# Schematic.net
KiCad netlist of a schematic drawn in EAGLE
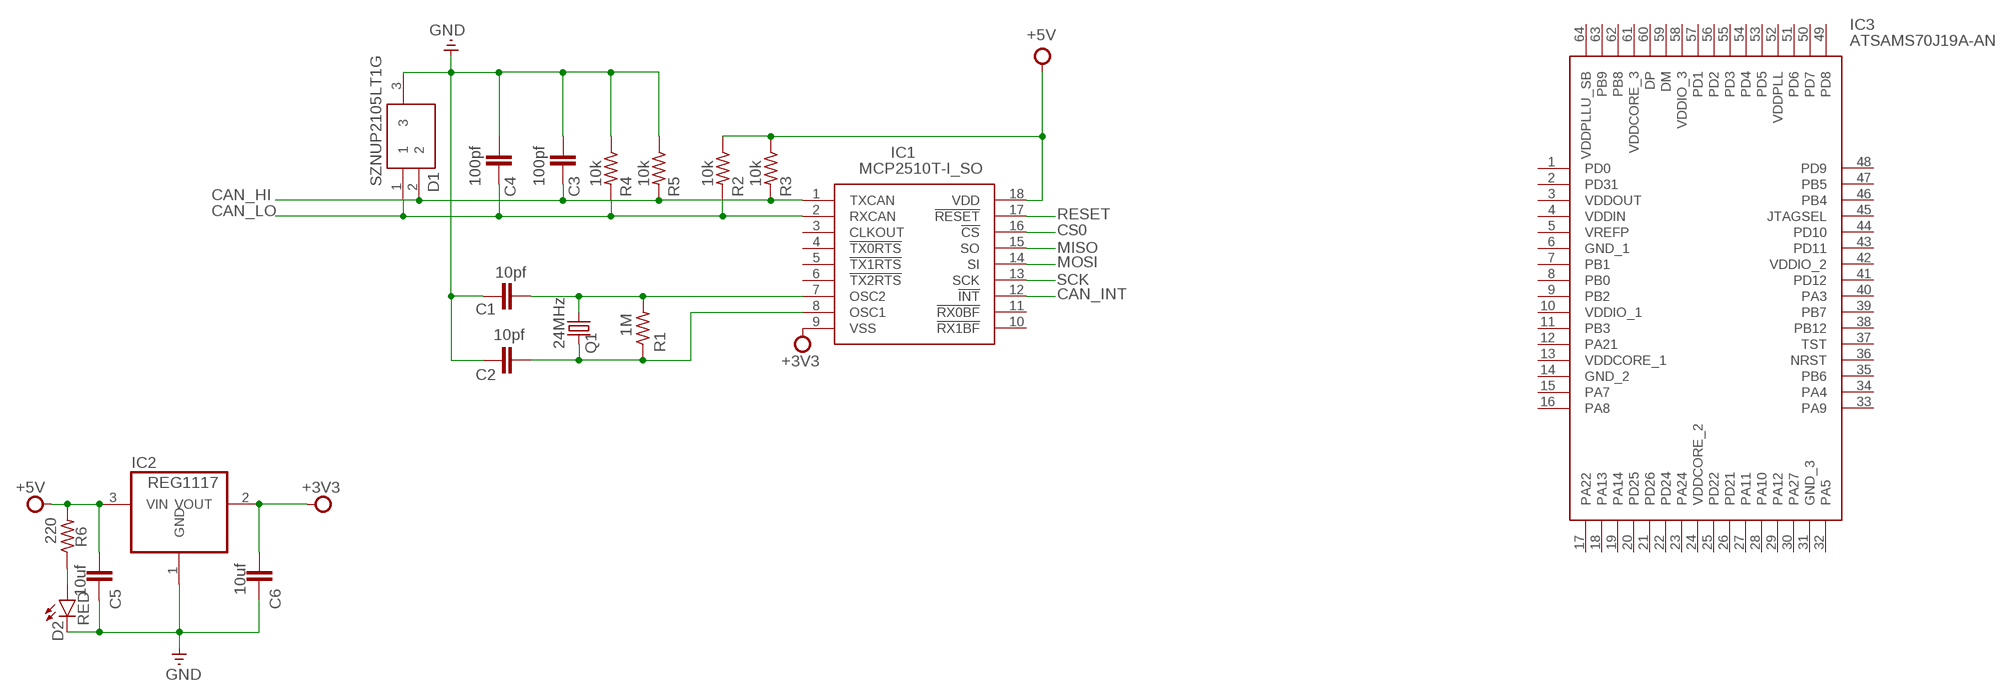
[diagram p0: schematic, sheet 1]

(export (version "E")
  (design (tool "Eeschema 10.0.6"))
  (components
    (comp (ref "C1")
      (value "10pf")
      (footprint "eagle-import:C2.5-3")
      (libsource (lib "eagle-import") (part "C2,5-3"))
    )
    (comp (ref "C2")
      (value "10pf")
      (footprint "eagle-import:C2.5-3")
      (libsource (lib "eagle-import") (part "C2,5-3"))
    )
    (comp (ref "C3")
      (value "100pf")
      (footprint "eagle-import:C2.5-3")
      (libsource (lib "eagle-import") (part "C2,5-3"))
    )
    (comp (ref "C4")
      (value "100pf")
      (footprint "eagle-import:C2.5-3")
      (libsource (lib "eagle-import") (part "C2,5-3"))
    )
    (comp (ref "C5")
      (value "10uf")
      (footprint "eagle-import:C2.5-3")
      (libsource (lib "eagle-import") (part "C2,5-3"))
    )
    (comp (ref "C6")
      (value "10uf")
      (footprint "eagle-import:C2.5-3")
      (libsource (lib "eagle-import") (part "C2,5-3"))
    )
    (comp (ref "D1")
      (value "SZNUP2105LT1G")
      (footprint "eagle-import:SOT96P237X111-3N")
      (fields (field (name "MOUSER_PART_NUMBER") "863-SZNUP2105LT1G"))
      (libsource (lib "eagle-import") (part "SZNUP2105LT1G"))
    )
    (comp (ref "D2")
      (value "RED")
      (footprint "eagle-import:LED-0402")
      (libsource (lib "eagle-import") (part "LED-RED_0402"))
    )
    (comp (ref "IC1")
      (value "MCP2510T-I_SO")
      (footprint "eagle-import:SOIC127P1030X265-18N")
      (fields
        (field (name "MANUFACTURER_PART_NUMBER") "MCP2510T-I/SO")
        (field (name "MOUSER_PART_NUMBER") "579-MCP2510T-I/SO")
      )
      (libsource (lib "eagle-import") (part "MCP2510T-I_SO"))
    )
    (comp (ref "IC2")
      (value "REG1117")
      (footprint "eagle-import:SOT223")
      (libsource (lib "eagle-import") (part "REG1117"))
    )
    (comp (ref "IC3")
      (value "ATSAMS70J19A-AN")
      (footprint "eagle-import:QFP50P1200X1200X160-64N")
      (fields (field (name "MOUSER_PART_NUMBER") "556-ATSAMS70J19A-AN"))
      (libsource (lib "eagle-import") (part "ATSAMS70J19A-AN"))
    )
    (comp (ref "Q1")
      (value "24MHz")
      (footprint "eagle-import:HC49_S")
      (libsource (lib "eagle-import") (part "CRYSTALHC49S"))
    )
    (comp (ref "R1")
      (value "1M")
      (footprint "eagle-import:0204_5")
      (libsource (lib "eagle-import") (part "R-US_0204/5"))
    )
    (comp (ref "R2")
      (value "10k")
      (footprint "eagle-import:0204_5")
      (libsource (lib "eagle-import") (part "R-US_0204/5"))
    )
    (comp (ref "R3")
      (value "10k")
      (footprint "eagle-import:0204_5")
      (libsource (lib "eagle-import") (part "R-US_0204/5"))
    )
    (comp (ref "R4")
      (value "10k")
      (footprint "eagle-import:0204_5")
      (libsource (lib "eagle-import") (part "R-US_0204/5"))
    )
    (comp (ref "R5")
      (value "10k")
      (footprint "eagle-import:0204_5")
      (libsource (lib "eagle-import") (part "R-US_0204/5"))
    )
    (comp (ref "R6")
      (value "220")
      (footprint "eagle-import:0204_5")
      (libsource (lib "eagle-import") (part "R-US_0204/5"))
    )
  )
  (nets
    (net (code "1") (name "+3V3") (class "Default")
      (node (ref "C6") (pin "1") (pinfunction "1_1") (pintype "passive"))
      (node (ref "IC1") (pin "9") (pinfunction "VSS_9") (pintype "power_in"))
      (node (ref "IC2") (pin "2") (pinfunction "VOUT_2") (pintype "output"))
    )
    (net (code "2") (name "+5V") (class "Default")
      (node (ref "C5") (pin "1") (pinfunction "1_1") (pintype "passive"))
      (node (ref "IC1") (pin "18") (pinfunction "VDD_18") (pintype "power_in"))
      (node (ref "IC2") (pin "3") (pinfunction "VIN_3") (pintype "input"))
      (node (ref "R2") (pin "1") (pinfunction "1_1") (pintype "passive"))
      (node (ref "R3") (pin "1") (pinfunction "1_1") (pintype "passive"))
      (node (ref "R6") (pin "2") (pinfunction "2_2") (pintype "passive"))
    )
    (net (code "3") (name "/CAN_HI") (class "Default")
      (node (ref "C3") (pin "1") (pinfunction "1_1") (pintype "passive"))
      (node (ref "D1") (pin "2") (pinfunction "2_2") (pintype "bidirectional"))
      (node (ref "IC1") (pin "1") (pinfunction "TXCAN_1") (pintype "bidirectional"))
      (node (ref "R3") (pin "2") (pinfunction "2_2") (pintype "passive"))
      (node (ref "R5") (pin "2") (pinfunction "2_2") (pintype "passive"))
    )
    (net (code "4") (name "/CAN_INT") (class "Default")
      (node (ref "IC1") (pin "12") (pinfunction "~{INT}_12") (pintype "input"))
    )
    (net (code "5") (name "/CAN_LO") (class "Default")
      (node (ref "C4") (pin "1") (pinfunction "1_1") (pintype "passive"))
      (node (ref "D1") (pin "1") (pinfunction "1_1") (pintype "bidirectional"))
      (node (ref "IC1") (pin "2") (pinfunction "RXCAN_2") (pintype "bidirectional"))
      (node (ref "R2") (pin "2") (pinfunction "2_2") (pintype "passive"))
      (node (ref "R4") (pin "2") (pinfunction "2_2") (pintype "passive"))
    )
    (net (code "6") (name "/CS0") (class "Default")
      (node (ref "IC1") (pin "16") (pinfunction "~{CS}_16") (pintype "input"))
    )
    (net (code "7") (name "/MISO") (class "Default")
      (node (ref "IC1") (pin "15") (pinfunction "SO_15") (pintype "bidirectional"))
    )
    (net (code "8") (name "/MOSI") (class "Default")
      (node (ref "IC1") (pin "14") (pinfunction "SI_14") (pintype "bidirectional"))
    )
    (net (code "9") (name "/RESET") (class "Default")
      (node (ref "IC1") (pin "17") (pinfunction "~{RESET}_17") (pintype "bidirectional"))
    )
    (net (code "10") (name "/SCK") (class "Default")
      (node (ref "IC1") (pin "13") (pinfunction "SCK_13") (pintype "bidirectional"))
    )
    (net (code "11") (name "GND") (class "Default")
      (node (ref "C1") (pin "1") (pinfunction "1_1") (pintype "passive"))
      (node (ref "C2") (pin "1") (pinfunction "1_1") (pintype "passive"))
      (node (ref "C3") (pin "2") (pinfunction "2_2") (pintype "passive"))
      (node (ref "C4") (pin "2") (pinfunction "2_2") (pintype "passive"))
      (node (ref "C5") (pin "2") (pinfunction "2_2") (pintype "passive"))
      (node (ref "C6") (pin "2") (pinfunction "2_2") (pintype "passive"))
      (node (ref "D1") (pin "3") (pinfunction "3_3") (pintype "bidirectional"))
      (node (ref "D2") (pin "C") (pinfunction "C_C") (pintype "passive"))
      (node (ref "IC2") (pin "1") (pinfunction "GND_1") (pintype "power_in"))
      (node (ref "R4") (pin "1") (pinfunction "1_1") (pintype "passive"))
      (node (ref "R5") (pin "1") (pinfunction "1_1") (pintype "passive"))
    )
    (net (code "12") (name "Net-(D2-PadA)") (class "Default")
      (node (ref "D2") (pin "A") (pinfunction "A_A") (pintype "passive"))
      (node (ref "R6") (pin "1") (pinfunction "1_1") (pintype "passive"))
    )
    (net (code "13") (name "Net-(IC1-OSC1)") (class "Default")
      (node (ref "C2") (pin "2") (pinfunction "2_2") (pintype "passive"))
      (node (ref "IC1") (pin "8") (pinfunction "OSC1_8") (pintype "bidirectional"))
      (node (ref "Q1") (pin "1") (pinfunction "1_1") (pintype "passive"))
      (node (ref "R1") (pin "1") (pinfunction "1_1") (pintype "passive"))
    )
    (net (code "14") (name "Net-(IC1-OSC2)") (class "Default")
      (node (ref "C1") (pin "2") (pinfunction "2_2") (pintype "passive"))
      (node (ref "IC1") (pin "7") (pinfunction "OSC2_7") (pintype "bidirectional"))
      (node (ref "Q1") (pin "2") (pinfunction "2_2") (pintype "passive"))
      (node (ref "R1") (pin "2") (pinfunction "2_2") (pintype "passive"))
    )
    (net (code "15") (name "unconnected-(IC1-CLKOUT-Pad3)") (class "Default")
      (node (ref "IC1") (pin "3") (pinfunction "CLKOUT_3") (pintype "output"))
    )
    (net (code "16") (name "unconnected-(IC1-~{RX0BF}-Pad11)") (class "Default")
      (node (ref "IC1") (pin "11") (pinfunction "~{RX0BF}_11") (pintype "bidirectional"))
    )
    (net (code "17") (name "unconnected-(IC1-~{RX1BF}-Pad10)") (class "Default")
      (node (ref "IC1") (pin "10") (pinfunction "~{RX1BF}_10") (pintype "bidirectional"))
    )
    (net (code "18") (name "unconnected-(IC1-~{TX0RTS}-Pad4)") (class "Default")
      (node (ref "IC1") (pin "4") (pinfunction "~{TX0RTS}_4") (pintype "bidirectional"))
    )
    (net (code "19") (name "unconnected-(IC1-~{TX1RTS}-Pad5)") (class "Default")
      (node (ref "IC1") (pin "5") (pinfunction "~{TX1RTS}_5") (pintype "bidirectional"))
    )
    (net (code "20") (name "unconnected-(IC1-~{TX2RTS}-Pad6)") (class "Default")
      (node (ref "IC1") (pin "6") (pinfunction "~{TX2RTS}_6") (pintype "bidirectional"))
    )
    (net (code "21") (name "unconnected-(IC3-DM-Pad59)") (class "Default")
      (node (ref "IC3") (pin "59") (pinfunction "DM_59") (pintype "bidirectional"))
    )
    (net (code "22") (name "unconnected-(IC3-DP-Pad60)") (class "Default")
      (node (ref "IC3") (pin "60") (pinfunction "DP_60") (pintype "bidirectional"))
    )
    (net (code "23") (name "unconnected-(IC3-GND_1-Pad6)") (class "Default")
      (node (ref "IC3") (pin "6") (pinfunction "GND_1_6") (pintype "bidirectional"))
    )
    (net (code "24") (name "unconnected-(IC3-GND_2-Pad14)") (class "Default")
      (node (ref "IC3") (pin "14") (pinfunction "GND_2_14") (pintype "bidirectional"))
    )
    (net (code "25") (name "unconnected-(IC3-GND_3-Pad31)") (class "Default")
      (node (ref "IC3") (pin "31") (pinfunction "GND_3_31") (pintype "bidirectional"))
    )
    (net (code "26") (name "unconnected-(IC3-JTAGSEL-Pad45)") (class "Default")
      (node (ref "IC3") (pin "45") (pinfunction "JTAGSEL_45") (pintype "bidirectional"))
    )
    (net (code "27") (name "unconnected-(IC3-NRST-Pad36)") (class "Default")
      (node (ref "IC3") (pin "36") (pinfunction "NRST_36") (pintype "bidirectional"))
    )
    (net (code "28") (name "unconnected-(IC3-PA3-Pad40)") (class "Default")
      (node (ref "IC3") (pin "40") (pinfunction "PA3_40") (pintype "bidirectional"))
    )
    (net (code "29") (name "unconnected-(IC3-PA4-Pad34)") (class "Default")
      (node (ref "IC3") (pin "34") (pinfunction "PA4_34") (pintype "bidirectional"))
    )
    (net (code "30") (name "unconnected-(IC3-PA5-Pad32)") (class "Default")
      (node (ref "IC3") (pin "32") (pinfunction "PA5_32") (pintype "bidirectional"))
    )
    (net (code "31") (name "unconnected-(IC3-PA7-Pad15)") (class "Default")
      (node (ref "IC3") (pin "15") (pinfunction "PA7_15") (pintype "bidirectional"))
    )
    (net (code "32") (name "unconnected-(IC3-PA8-Pad16)") (class "Default")
      (node (ref "IC3") (pin "16") (pinfunction "PA8_16") (pintype "bidirectional"))
    )
    (net (code "33") (name "unconnected-(IC3-PA9-Pad33)") (class "Default")
      (node (ref "IC3") (pin "33") (pinfunction "PA9_33") (pintype "bidirectional"))
    )
    (net (code "34") (name "unconnected-(IC3-PA10-Pad28)") (class "Default")
      (node (ref "IC3") (pin "28") (pinfunction "PA10_28") (pintype "bidirectional"))
    )
    (net (code "35") (name "unconnected-(IC3-PA11-Pad27)") (class "Default")
      (node (ref "IC3") (pin "27") (pinfunction "PA11_27") (pintype "bidirectional"))
    )
    (net (code "36") (name "unconnected-(IC3-PA12-Pad29)") (class "Default")
      (node (ref "IC3") (pin "29") (pinfunction "PA12_29") (pintype "bidirectional"))
    )
    (net (code "37") (name "unconnected-(IC3-PA13-Pad18)") (class "Default")
      (node (ref "IC3") (pin "18") (pinfunction "PA13_18") (pintype "bidirectional"))
    )
    (net (code "38") (name "unconnected-(IC3-PA14-Pad19)") (class "Default")
      (node (ref "IC3") (pin "19") (pinfunction "PA14_19") (pintype "bidirectional"))
    )
    (net (code "39") (name "unconnected-(IC3-PA21-Pad12)") (class "Default")
      (node (ref "IC3") (pin "12") (pinfunction "PA21_12") (pintype "bidirectional"))
    )
    (net (code "40") (name "unconnected-(IC3-PA22-Pad17)") (class "Default")
      (node (ref "IC3") (pin "17") (pinfunction "PA22_17") (pintype "bidirectional"))
    )
    (net (code "41") (name "unconnected-(IC3-PA24-Pad23)") (class "Default")
      (node (ref "IC3") (pin "23") (pinfunction "PA24_23") (pintype "bidirectional"))
    )
    (net (code "42") (name "unconnected-(IC3-PA27-Pad30)") (class "Default")
      (node (ref "IC3") (pin "30") (pinfunction "PA27_30") (pintype "bidirectional"))
    )
    (net (code "43") (name "unconnected-(IC3-PB0-Pad8)") (class "Default")
      (node (ref "IC3") (pin "8") (pinfunction "PB0_8") (pintype "bidirectional"))
    )
    (net (code "44") (name "unconnected-(IC3-PB1-Pad7)") (class "Default")
      (node (ref "IC3") (pin "7") (pinfunction "PB1_7") (pintype "bidirectional"))
    )
    (net (code "45") (name "unconnected-(IC3-PB2-Pad9)") (class "Default")
      (node (ref "IC3") (pin "9") (pinfunction "PB2_9") (pintype "bidirectional"))
    )
    (net (code "46") (name "unconnected-(IC3-PB3-Pad11)") (class "Default")
      (node (ref "IC3") (pin "11") (pinfunction "PB3_11") (pintype "bidirectional"))
    )
    (net (code "47") (name "unconnected-(IC3-PB4-Pad46)") (class "Default")
      (node (ref "IC3") (pin "46") (pinfunction "PB4_46") (pintype "bidirectional"))
    )
    (net (code "48") (name "unconnected-(IC3-PB5-Pad47)") (class "Default")
      (node (ref "IC3") (pin "47") (pinfunction "PB5_47") (pintype "bidirectional"))
    )
    (net (code "49") (name "unconnected-(IC3-PB6-Pad35)") (class "Default")
      (node (ref "IC3") (pin "35") (pinfunction "PB6_35") (pintype "bidirectional"))
    )
    (net (code "50") (name "unconnected-(IC3-PB7-Pad39)") (class "Default")
      (node (ref "IC3") (pin "39") (pinfunction "PB7_39") (pintype "bidirectional"))
    )
    (net (code "51") (name "unconnected-(IC3-PB8-Pad62)") (class "Default")
      (node (ref "IC3") (pin "62") (pinfunction "PB8_62") (pintype "bidirectional"))
    )
    (net (code "52") (name "unconnected-(IC3-PB9-Pad63)") (class "Default")
      (node (ref "IC3") (pin "63") (pinfunction "PB9_63") (pintype "bidirectional"))
    )
    (net (code "53") (name "unconnected-(IC3-PB12-Pad38)") (class "Default")
      (node (ref "IC3") (pin "38") (pinfunction "PB12_38") (pintype "bidirectional"))
    )
    (net (code "54") (name "unconnected-(IC3-PD0-Pad1)") (class "Default")
      (node (ref "IC3") (pin "1") (pinfunction "PD0_1") (pintype "bidirectional"))
    )
    (net (code "55") (name "unconnected-(IC3-PD1-Pad57)") (class "Default")
      (node (ref "IC3") (pin "57") (pinfunction "PD1_57") (pintype "bidirectional"))
    )
    (net (code "56") (name "unconnected-(IC3-PD2-Pad56)") (class "Default")
      (node (ref "IC3") (pin "56") (pinfunction "PD2_56") (pintype "bidirectional"))
    )
    (net (code "57") (name "unconnected-(IC3-PD3-Pad55)") (class "Default")
      (node (ref "IC3") (pin "55") (pinfunction "PD3_55") (pintype "bidirectional"))
    )
    (net (code "58") (name "unconnected-(IC3-PD4-Pad54)") (class "Default")
      (node (ref "IC3") (pin "54") (pinfunction "PD4_54") (pintype "bidirectional"))
    )
    (net (code "59") (name "unconnected-(IC3-PD5-Pad53)") (class "Default")
      (node (ref "IC3") (pin "53") (pinfunction "PD5_53") (pintype "bidirectional"))
    )
    (net (code "60") (name "unconnected-(IC3-PD6-Pad51)") (class "Default")
      (node (ref "IC3") (pin "51") (pinfunction "PD6_51") (pintype "bidirectional"))
    )
    (net (code "61") (name "unconnected-(IC3-PD7-Pad50)") (class "Default")
      (node (ref "IC3") (pin "50") (pinfunction "PD7_50") (pintype "bidirectional"))
    )
    (net (code "62") (name "unconnected-(IC3-PD8-Pad49)") (class "Default")
      (node (ref "IC3") (pin "49") (pinfunction "PD8_49") (pintype "bidirectional"))
    )
    (net (code "63") (name "unconnected-(IC3-PD9-Pad48)") (class "Default")
      (node (ref "IC3") (pin "48") (pinfunction "PD9_48") (pintype "bidirectional"))
    )
    (net (code "64") (name "unconnected-(IC3-PD10-Pad44)") (class "Default")
      (node (ref "IC3") (pin "44") (pinfunction "PD10_44") (pintype "bidirectional"))
    )
    (net (code "65") (name "unconnected-(IC3-PD11-Pad43)") (class "Default")
      (node (ref "IC3") (pin "43") (pinfunction "PD11_43") (pintype "bidirectional"))
    )
    (net (code "66") (name "unconnected-(IC3-PD12-Pad41)") (class "Default")
      (node (ref "IC3") (pin "41") (pinfunction "PD12_41") (pintype "bidirectional"))
    )
    (net (code "67") (name "unconnected-(IC3-PD21-Pad26)") (class "Default")
      (node (ref "IC3") (pin "26") (pinfunction "PD21_26") (pintype "bidirectional"))
    )
    (net (code "68") (name "unconnected-(IC3-PD22-Pad25)") (class "Default")
      (node (ref "IC3") (pin "25") (pinfunction "PD22_25") (pintype "bidirectional"))
    )
    (net (code "69") (name "unconnected-(IC3-PD24-Pad22)") (class "Default")
      (node (ref "IC3") (pin "22") (pinfunction "PD24_22") (pintype "bidirectional"))
    )
    (net (code "70") (name "unconnected-(IC3-PD25-Pad20)") (class "Default")
      (node (ref "IC3") (pin "20") (pinfunction "PD25_20") (pintype "bidirectional"))
    )
    (net (code "71") (name "unconnected-(IC3-PD26-Pad21)") (class "Default")
      (node (ref "IC3") (pin "21") (pinfunction "PD26_21") (pintype "bidirectional"))
    )
    (net (code "72") (name "unconnected-(IC3-PD31-Pad2)") (class "Default")
      (node (ref "IC3") (pin "2") (pinfunction "PD31_2") (pintype "bidirectional"))
    )
    (net (code "73") (name "unconnected-(IC3-TST-Pad37)") (class "Default")
      (node (ref "IC3") (pin "37") (pinfunction "TST_37") (pintype "bidirectional"))
    )
    (net (code "74") (name "unconnected-(IC3-VDDCORE_1-Pad13)") (class "Default")
      (node (ref "IC3") (pin "13") (pinfunction "VDDCORE_1_13") (pintype "bidirectional"))
    )
    (net (code "75") (name "unconnected-(IC3-VDDCORE_2-Pad24)") (class "Default")
      (node (ref "IC3") (pin "24") (pinfunction "VDDCORE_2_24") (pintype "bidirectional"))
    )
    (net (code "76") (name "unconnected-(IC3-VDDCORE_3-Pad61)") (class "Default")
      (node (ref "IC3") (pin "61") (pinfunction "VDDCORE_3_61") (pintype "bidirectional"))
    )
    (net (code "77") (name "unconnected-(IC3-VDDIN-Pad4)") (class "Default")
      (node (ref "IC3") (pin "4") (pinfunction "VDDIN_4") (pintype "bidirectional"))
    )
    (net (code "78") (name "unconnected-(IC3-VDDIO_1-Pad10)") (class "Default")
      (node (ref "IC3") (pin "10") (pinfunction "VDDIO_1_10") (pintype "bidirectional"))
    )
    (net (code "79") (name "unconnected-(IC3-VDDIO_2-Pad42)") (class "Default")
      (node (ref "IC3") (pin "42") (pinfunction "VDDIO_2_42") (pintype "bidirectional"))
    )
    (net (code "80") (name "unconnected-(IC3-VDDIO_3-Pad58)") (class "Default")
      (node (ref "IC3") (pin "58") (pinfunction "VDDIO_3_58") (pintype "bidirectional"))
    )
    (net (code "81") (name "unconnected-(IC3-VDDOUT-Pad3)") (class "Default")
      (node (ref "IC3") (pin "3") (pinfunction "VDDOUT_3") (pintype "bidirectional"))
    )
    (net (code "82") (name "unconnected-(IC3-VDDPLL-Pad52)") (class "Default")
      (node (ref "IC3") (pin "52") (pinfunction "VDDPLL_52") (pintype "bidirectional"))
    )
    (net (code "83") (name "unconnected-(IC3-VDDPLLU_SB-Pad64)") (class "Default")
      (node (ref "IC3") (pin "64") (pinfunction "VDDPLLU_SB_64") (pintype "bidirectional"))
    )
    (net (code "84") (name "unconnected-(IC3-VREFP-Pad5)") (class "Default")
      (node (ref "IC3") (pin "5") (pinfunction "VREFP_5") (pintype "bidirectional"))
    )
  )
)
